# 10-DPLL-1.net
KiCad netlist of a schematic drawn in Altium Designer
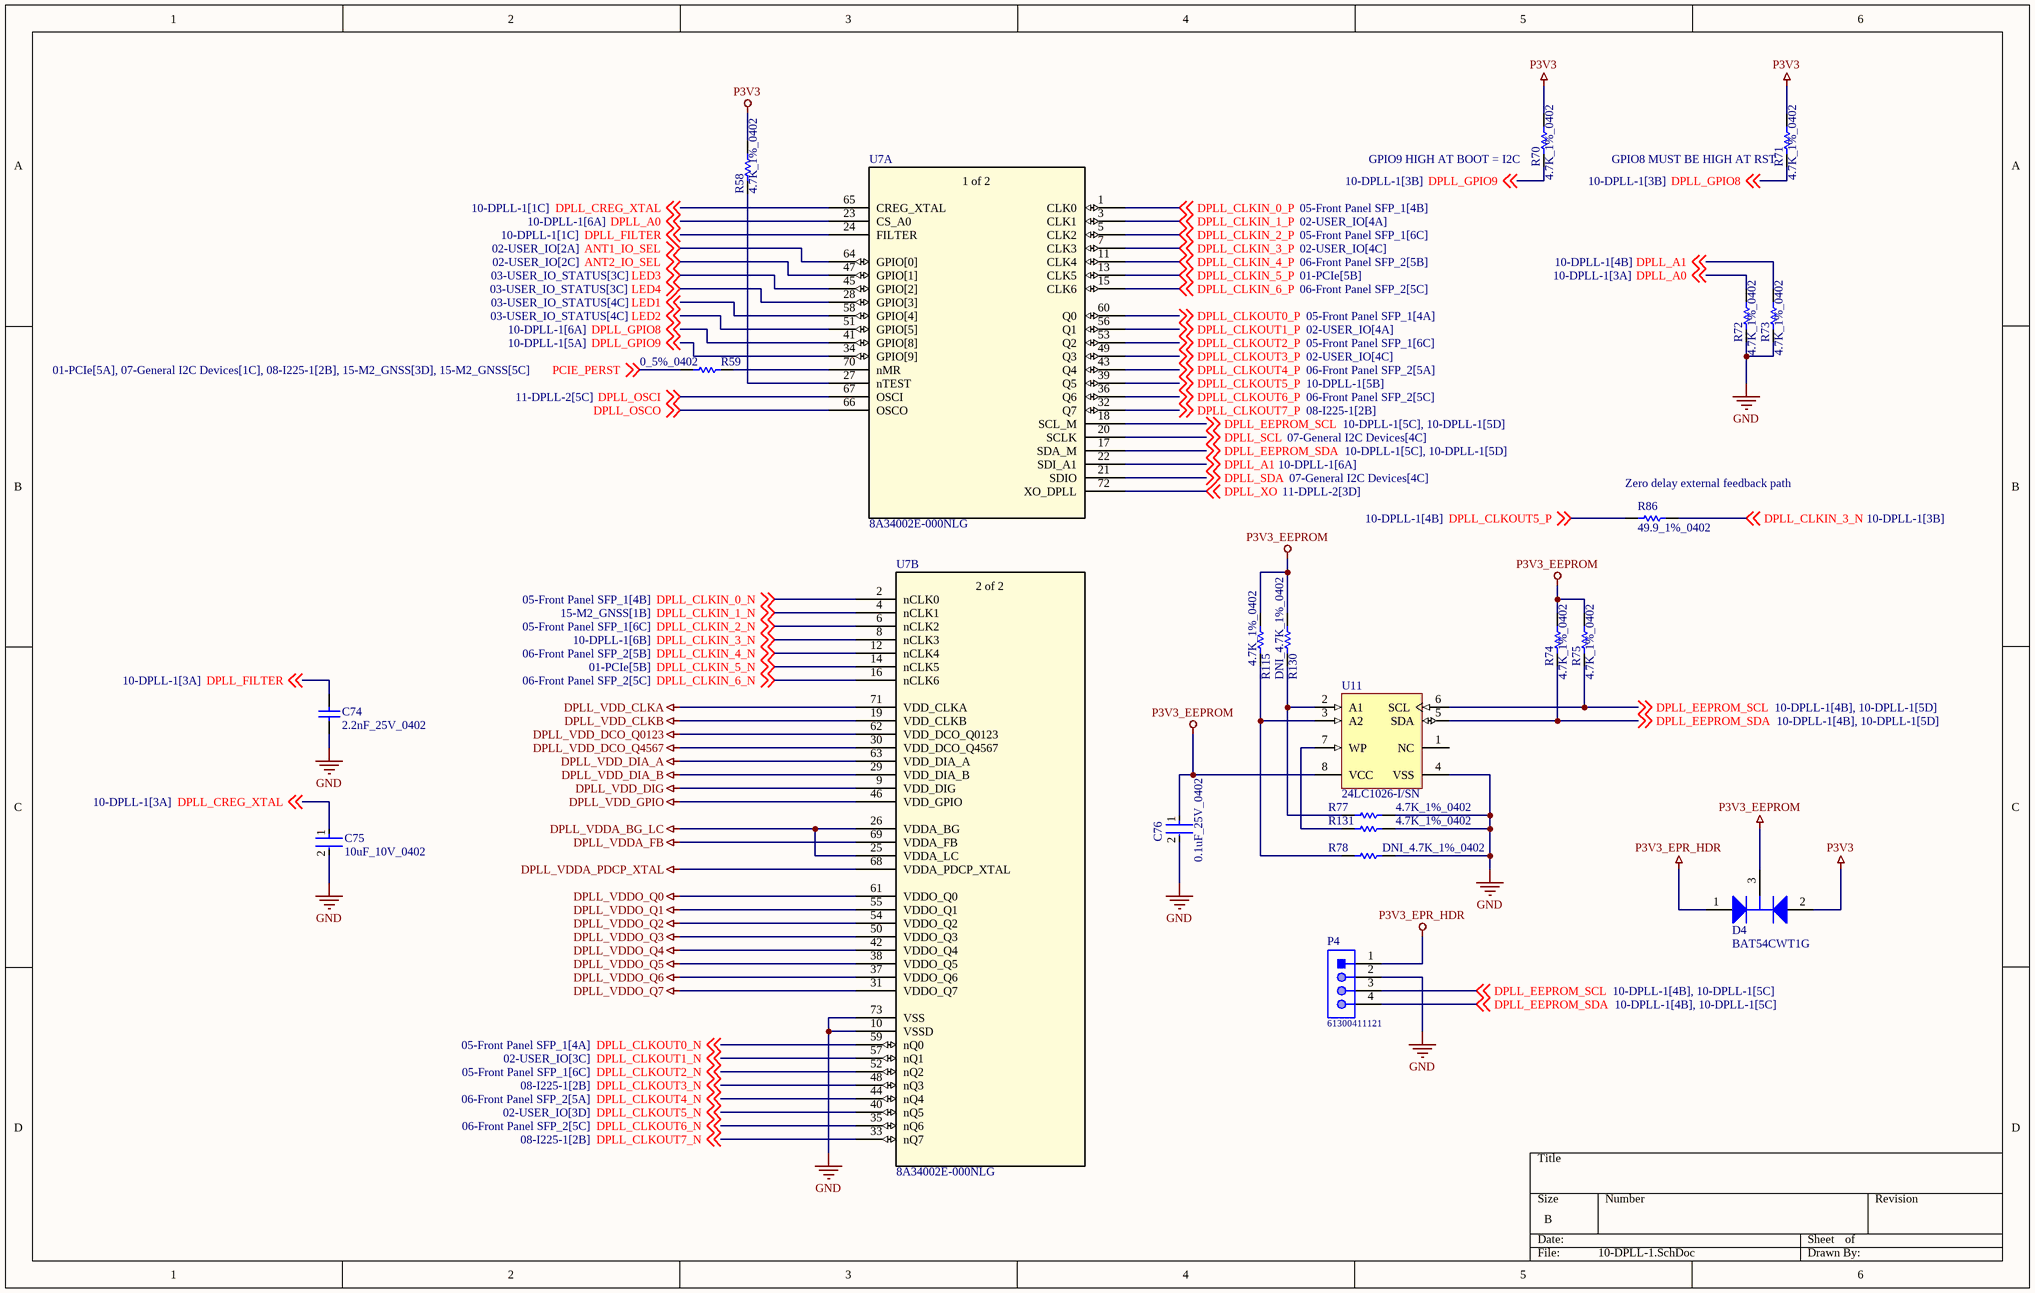
[diagram p0: 10-DPLL-1.SchDoc]

(export (version "E")
  (design (tool "Eeschema 10.0.6"))
  (components
    (comp (ref "C74")
      (value "2.2nF_25V_0402")
      (footprint "CAPC1005X56X25LL10T15")
      (fields
        (field (name "MANUFACTURER") "AVX Interconnect / Elco")
        (field (name "PART NUMBER") "04025C222JAT2A")
      )
      (libsource (lib "Altium Content Vault") (part "CAP"))
    )
    (comp (ref "C75")
      (value "10uF_10V_0402")
      (footprint "FP-CL05A106MP5NUNC-MFG")
      (description "CAP CER 10UF 10V X5R 0402")
      (fields
        (field (name "OCTOPART") "https://octopart.com/cl05a106mp5nunc-samsung-22457395")
        (field (name "TOLERANCE") "20%")
      )
      (libsource (lib "Altium Content Vault") (part "b4654b650e69147ec39a6b967a45e02"))
    )
    (comp (ref "C76")
      (value "0.1uF_25V_0402")
      (footprint "FP-0402-L_1_0_1-W_0_5_0_1-IPC_C")
      (description "General Purpose Ceramic Capacitor, 0402, 100nF, 10%, X7R, 15%, 25V")
      (fields (field (name "VOLTAGE") "25V") (field (name "TOLERANCE") "10%"))
      (libsource (lib "Altium Content Vault") (part "b4654b650e69147ec39a6b967a45e02"))
    )
    (comp (ref "D4")
      (value "BAT54CWT1G")
      (footprint "ONSC-SOT-323-3-419-04_V")
      (description "Dual Series Cathode Schottky Barrier Diodes, 3-Pin SOT-323, Pb-Free, Tape and Reel")
      (fields (field (name "MANUFACTURER") "On Semiconductor"))
      (libsource (lib "Altium Content Vault") (part "ONSC-D-A1A2K3-3"))
    )
    (comp (ref "P4")
      (value "61300411121")
      (footprint "61300411121")
      (description "THT Vertical Pin Header WR-PHD, Pitch 2.54 mm, Single Row, 4 pins")
      (fields (field (name "MANUFACTURER") "Wurth Elektronik") (field (name "PUBLISHER") "WurthElektronik"))
      (libsource (lib "Altium Content Vault") (part "WE-CN-1P-M-R4"))
    )
    (comp (ref "R58")
      (value "4.7K_1%_0402")
      (footprint "RESC1005X40X25NL10T10")
      (fields (field (name "MANUFACTURER") "Bourns") (field (name "PART NUMBER") "CR0402-FX-4701GLF"))
      (libsource (lib "Altium Content Vault") (part "RES"))
    )
    (comp (ref "R59")
      (value "0_5%_0402")
      (footprint "RESC1005X40X25LL10T10")
      (fields (field (name "MANUFACTURER") "KOA Speer") (field (name "PART NUMBER") "RK73Z1ETTP"))
      (libsource (lib "Altium Content Vault") (part "RES"))
    )
    (comp (ref "R70")
      (value "4.7K_1%_0402")
      (footprint "RESC1005X40X25NL10T10")
      (fields (field (name "MANUFACTURER") "Bourns") (field (name "PART NUMBER") "CR0402-FX-4701GLF"))
      (libsource (lib "Altium Content Vault") (part "RES"))
    )
    (comp (ref "R71")
      (value "4.7K_1%_0402")
      (footprint "RESC1005X40X25NL10T10")
      (fields (field (name "MANUFACTURER") "Bourns") (field (name "PART NUMBER") "CR0402-FX-4701GLF"))
      (libsource (lib "Altium Content Vault") (part "RES"))
    )
    (comp (ref "R72")
      (value "4.7K_1%_0402")
      (footprint "RESC1005X40X25NL10T10")
      (fields (field (name "MANUFACTURER") "Bourns") (field (name "PART NUMBER") "CR0402-FX-4701GLF"))
      (libsource (lib "Altium Content Vault") (part "RES"))
    )
    (comp (ref "R73")
      (value "4.7K_1%_0402")
      (footprint "RESC1005X40X25NL10T10")
      (fields (field (name "MANUFACTURER") "Bourns") (field (name "PART NUMBER") "CR0402-FX-4701GLF"))
      (libsource (lib "Altium Content Vault") (part "RES"))
    )
    (comp (ref "R74")
      (value "4.7K_1%_0402")
      (footprint "RESC1005X40X25NL10T10")
      (fields (field (name "MANUFACTURER") "Bourns") (field (name "PART NUMBER") "CR0402-FX-4701GLF"))
      (libsource (lib "Altium Content Vault") (part "RES"))
    )
    (comp (ref "R75")
      (value "4.7K_1%_0402")
      (footprint "RESC1005X40X25NL10T10")
      (fields (field (name "MANUFACTURER") "Bourns") (field (name "PART NUMBER") "CR0402-FX-4701GLF"))
      (libsource (lib "Altium Content Vault") (part "RES"))
    )
    (comp (ref "R77")
      (value "4.7K_1%_0402")
      (footprint "RESC1005X40X25NL10T10")
      (fields (field (name "MANUFACTURER") "Bourns") (field (name "PART NUMBER") "CR0402-FX-4701GLF"))
      (libsource (lib "Altium Content Vault") (part "RES"))
    )
    (comp (ref "R78")
      (value "DNI_4.7K_1%_0402")
      (footprint "RESC1005X40X25NL10T10")
      (fields (field (name "MANUFACTURER") "Bourns") (field (name "PART NUMBER") "CR0402-FX-4701GLF"))
      (libsource (lib "Altium Content Vault") (part "RES"))
    )
    (comp (ref "R86")
      (value "49.9_1%_0402")
      (footprint "RESC1005X40X25NL10T10")
      (fields (field (name "PART NUMBER") "RK73H1ETTP49R9F") (field (name "MANUFACTURER") "KOA Speer"))
      (libsource (lib "Altium Content Vault") (part "RES"))
    )
    (comp (ref "R115")
      (value "4.7K_1%_0402")
      (footprint "RESC1005X40X25NL10T10")
      (fields (field (name "MANUFACTURER") "Bourns") (field (name "PART NUMBER") "CR0402-FX-4701GLF"))
      (libsource (lib "Altium Content Vault") (part "RES"))
    )
    (comp (ref "R130")
      (value "DNI_4.7K_1%_0402")
      (footprint "RESC1005X40X25NL10T10")
      (fields (field (name "MANUFACTURER") "Bourns") (field (name "PART NUMBER") "CR0402-FX-4701GLF"))
      (libsource (lib "Altium Content Vault") (part "RES"))
    )
    (comp (ref "R131")
      (value "4.7K_1%_0402")
      (footprint "RESC1005X40X25NL10T10")
      (fields (field (name "MANUFACTURER") "Bourns") (field (name "PART NUMBER") "CR0402-FX-4701GLF"))
      (libsource (lib "Altium Content Vault") (part "RES"))
    )
    (comp (ref "U7")
      (value "8A34002E-000NLG")
      (footprint "QFN_2E-000NLG_REN")
      (description "No Description Available")
      (libsource (lib "8A34002E-000NLG") (part "8A34002E-000NLG"))
    )
    (comp (ref "U11")
      (value "24LC1026-I/SN")
      (footprint "MCHP-SOIC-SN8_N")
      (description "1024K bits I2C™ Serial EEPROM, 2.5 to 5.5 V, 400 kHz, -40 to 85 degC, 8-pin SOIC (SN8), Tube")
      (fields (field (name "MANUFACTURER") "Microchip"))
      (libsource (lib "Altium Content Vault") (part "MCHP-24LC1026-SOIC-8"))
    )
  )
  (nets
    (net (code "1") (name "ANT1_IO_SEL") (class "Default")
      (node (ref "U7") (pin "64") (pinfunction "GPIO[0]_64") (pintype "bidirectional"))
    )
    (net (code "2") (name "ANT2_IO_SEL") (class "Default")
      (node (ref "U7") (pin "47") (pinfunction "GPIO[1]_47") (pintype "bidirectional"))
    )
    (net (code "3") (name "DPLL_A0") (class "Default")
      (node (ref "R72") (pin "1") (pinfunction "1_1") (pintype "passive"))
      (node (ref "U7") (pin "23") (pinfunction "CS_A0_23") (pintype "passive"))
    )
    (net (code "4") (name "DPLL_A1") (class "Default")
      (node (ref "R73") (pin "1") (pinfunction "1_1") (pintype "passive"))
      (node (ref "U7") (pin "22") (pinfunction "SDI_A1_22") (pintype "passive"))
    )
    (net (code "5") (name "DPLL_CLKIN_0_N") (class "Default")
      (node (ref "U7") (pin "2") (pinfunction "nCLK0_2") (pintype "passive"))
    )
    (net (code "6") (name "DPLL_CLKIN_0_P") (class "Default")
      (node (ref "U7") (pin "1") (pinfunction "CLK0_1") (pintype "bidirectional"))
    )
    (net (code "7") (name "DPLL_CLKIN_1_N") (class "Default")
      (node (ref "U7") (pin "4") (pinfunction "nCLK1_4") (pintype "passive"))
    )
    (net (code "8") (name "DPLL_CLKIN_1_P") (class "Default")
      (node (ref "U7") (pin "3") (pinfunction "CLK1_3") (pintype "bidirectional"))
    )
    (net (code "9") (name "DPLL_CLKIN_2_N") (class "Default")
      (node (ref "U7") (pin "6") (pinfunction "nCLK2_6") (pintype "passive"))
    )
    (net (code "10") (name "DPLL_CLKIN_2_P") (class "Default")
      (node (ref "U7") (pin "5") (pinfunction "CLK2_5") (pintype "bidirectional"))
    )
    (net (code "11") (name "DPLL_CLKIN_3_N") (class "Default")
      (node (ref "R86") (pin "2") (pinfunction "2_2") (pintype "passive"))
      (node (ref "U7") (pin "8") (pinfunction "nCLK3_8") (pintype "passive"))
    )
    (net (code "12") (name "DPLL_CLKIN_3_P") (class "Default")
      (node (ref "U7") (pin "7") (pinfunction "CLK3_7") (pintype "bidirectional"))
    )
    (net (code "13") (name "DPLL_CLKIN_4_N") (class "Default")
      (node (ref "U7") (pin "12") (pinfunction "nCLK4_12") (pintype "passive"))
    )
    (net (code "14") (name "DPLL_CLKIN_4_P") (class "Default")
      (node (ref "U7") (pin "11") (pinfunction "CLK4_11") (pintype "bidirectional"))
    )
    (net (code "15") (name "DPLL_CLKIN_5_N") (class "Default")
      (node (ref "U7") (pin "14") (pinfunction "nCLK5_14") (pintype "passive"))
    )
    (net (code "16") (name "DPLL_CLKIN_5_P") (class "Default")
      (node (ref "U7") (pin "13") (pinfunction "CLK5_13") (pintype "bidirectional"))
    )
    (net (code "17") (name "DPLL_CLKIN_6_N") (class "Default")
      (node (ref "U7") (pin "16") (pinfunction "nCLK6_16") (pintype "passive"))
    )
    (net (code "18") (name "DPLL_CLKIN_6_P") (class "Default")
      (node (ref "U7") (pin "15") (pinfunction "CLK6_15") (pintype "bidirectional"))
    )
    (net (code "19") (name "DPLL_CLKOUT0_N") (class "Default")
      (node (ref "U7") (pin "59") (pinfunction "nQ0_59") (pintype "bidirectional"))
    )
    (net (code "20") (name "DPLL_CLKOUT0_P") (class "Default")
      (node (ref "U7") (pin "60") (pinfunction "Q0_60") (pintype "bidirectional"))
    )
    (net (code "21") (name "DPLL_CLKOUT1_N") (class "Default")
      (node (ref "U7") (pin "57") (pinfunction "nQ1_57") (pintype "bidirectional"))
    )
    (net (code "22") (name "DPLL_CLKOUT1_P") (class "Default")
      (node (ref "U7") (pin "56") (pinfunction "Q1_56") (pintype "bidirectional"))
    )
    (net (code "23") (name "DPLL_CLKOUT2_N") (class "Default")
      (node (ref "U7") (pin "52") (pinfunction "nQ2_52") (pintype "bidirectional"))
    )
    (net (code "24") (name "DPLL_CLKOUT2_P") (class "Default")
      (node (ref "U7") (pin "53") (pinfunction "Q2_53") (pintype "bidirectional"))
    )
    (net (code "25") (name "DPLL_CLKOUT3_N") (class "Default")
      (node (ref "U7") (pin "48") (pinfunction "nQ3_48") (pintype "bidirectional"))
    )
    (net (code "26") (name "DPLL_CLKOUT3_P") (class "Default")
      (node (ref "U7") (pin "49") (pinfunction "Q3_49") (pintype "bidirectional"))
    )
    (net (code "27") (name "DPLL_CLKOUT4_N") (class "Default")
      (node (ref "U7") (pin "44") (pinfunction "nQ4_44") (pintype "bidirectional"))
    )
    (net (code "28") (name "DPLL_CLKOUT4_P") (class "Default")
      (node (ref "U7") (pin "43") (pinfunction "Q4_43") (pintype "bidirectional"))
    )
    (net (code "29") (name "DPLL_CLKOUT5_N") (class "Default")
      (node (ref "U7") (pin "40") (pinfunction "nQ5_40") (pintype "bidirectional"))
    )
    (net (code "30") (name "DPLL_CLKOUT5_P") (class "Default")
      (node (ref "R86") (pin "1") (pinfunction "1_1") (pintype "passive"))
      (node (ref "U7") (pin "39") (pinfunction "Q5_39") (pintype "bidirectional"))
    )
    (net (code "31") (name "DPLL_CLKOUT6_N") (class "Default")
      (node (ref "U7") (pin "35") (pinfunction "nQ6_35") (pintype "bidirectional"))
    )
    (net (code "32") (name "DPLL_CLKOUT6_P") (class "Default")
      (node (ref "U7") (pin "36") (pinfunction "Q6_36") (pintype "bidirectional"))
    )
    (net (code "33") (name "DPLL_CLKOUT7_N") (class "Default")
      (node (ref "U7") (pin "33") (pinfunction "nQ7_33") (pintype "bidirectional"))
    )
    (net (code "34") (name "DPLL_CLKOUT7_P") (class "Default")
      (node (ref "U7") (pin "32") (pinfunction "Q7_32") (pintype "bidirectional"))
    )
    (net (code "35") (name "DPLL_CREG_XTAL") (class "Default")
      (node (ref "C75") (pin "1") (pinfunction "1_1") (pintype "passive"))
      (node (ref "U7") (pin "65") (pinfunction "CREG_XTAL_65") (pintype "passive"))
    )
    (net (code "36") (name "DPLL_EEPROM_SCL") (class "Default")
      (node (ref "P4") (pin "3") (pinfunction "3_3") (pintype "passive"))
      (node (ref "R75") (pin "2") (pinfunction "2_2") (pintype "passive"))
      (node (ref "U11") (pin "6") (pinfunction "SCL_6") (pintype "input"))
      (node (ref "U7") (pin "18") (pinfunction "SCL_M_18") (pintype "passive"))
    )
    (net (code "37") (name "DPLL_EEPROM_SDA") (class "Default")
      (node (ref "P4") (pin "4") (pinfunction "4_4") (pintype "passive"))
      (node (ref "R74") (pin "2") (pinfunction "2_2") (pintype "passive"))
      (node (ref "U11") (pin "5") (pinfunction "SDA_5") (pintype "bidirectional"))
      (node (ref "U7") (pin "17") (pinfunction "SDA_M_17") (pintype "passive"))
    )
    (net (code "38") (name "DPLL_FILTER") (class "Default")
      (node (ref "C74") (pin "2") (pinfunction "2_2") (pintype "passive"))
      (node (ref "U7") (pin "24") (pinfunction "FILTER_24") (pintype "passive"))
    )
    (net (code "39") (name "DPLL_GPIO8") (class "Default")
      (node (ref "R71") (pin "2") (pinfunction "2_2") (pintype "passive"))
      (node (ref "U7") (pin "41") (pinfunction "GPIO[8]_41") (pintype "bidirectional"))
    )
    (net (code "40") (name "DPLL_GPIO9") (class "Default")
      (node (ref "R70") (pin "2") (pinfunction "2_2") (pintype "passive"))
      (node (ref "U7") (pin "34") (pinfunction "GPIO[9]_34") (pintype "bidirectional"))
    )
    (net (code "41") (name "DPLL_OSCI") (class "Default")
      (node (ref "U7") (pin "67") (pinfunction "OSCI_67") (pintype "passive"))
    )
    (net (code "42") (name "DPLL_OSCO") (class "Default")
      (node (ref "U7") (pin "66") (pinfunction "OSCO_66") (pintype "passive"))
    )
    (net (code "43") (name "DPLL_SCL") (class "Default")
      (node (ref "U7") (pin "20") (pinfunction "SCLK_20") (pintype "passive"))
    )
    (net (code "44") (name "DPLL_SDA") (class "Default")
      (node (ref "U7") (pin "21") (pinfunction "SDIO_21") (pintype "passive"))
    )
    (net (code "45") (name "DPLL_VDDA_BG_LC") (class "Default")
      (node (ref "U7") (pin "25") (pinfunction "VDDA_LC_25") (pintype "power_in"))
      (node (ref "U7") (pin "26") (pinfunction "VDDA_BG_26") (pintype "power_in"))
    )
    (net (code "46") (name "DPLL_VDDA_FB") (class "Default")
      (node (ref "U7") (pin "69") (pinfunction "VDDA_FB_69") (pintype "power_in"))
    )
    (net (code "47") (name "DPLL_VDDA_PDCP_XTAL") (class "Default")
      (node (ref "U7") (pin "68") (pinfunction "VDDA_PDCP_XTAL_68") (pintype "power_in"))
    )
    (net (code "48") (name "DPLL_VDDO_Q0") (class "Default")
      (node (ref "U7") (pin "61") (pinfunction "VDDO_Q0_61") (pintype "power_in"))
    )
    (net (code "49") (name "DPLL_VDDO_Q1") (class "Default")
      (node (ref "U7") (pin "55") (pinfunction "VDDO_Q1_55") (pintype "power_in"))
    )
    (net (code "50") (name "DPLL_VDDO_Q2") (class "Default")
      (node (ref "U7") (pin "54") (pinfunction "VDDO_Q2_54") (pintype "power_in"))
    )
    (net (code "51") (name "DPLL_VDDO_Q3") (class "Default")
      (node (ref "U7") (pin "50") (pinfunction "VDDO_Q3_50") (pintype "power_in"))
    )
    (net (code "52") (name "DPLL_VDDO_Q4") (class "Default")
      (node (ref "U7") (pin "42") (pinfunction "VDDO_Q4_42") (pintype "power_in"))
    )
    (net (code "53") (name "DPLL_VDDO_Q5") (class "Default")
      (node (ref "U7") (pin "38") (pinfunction "VDDO_Q5_38") (pintype "power_in"))
    )
    (net (code "54") (name "DPLL_VDDO_Q6") (class "Default")
      (node (ref "U7") (pin "37") (pinfunction "VDDO_Q6_37") (pintype "power_in"))
    )
    (net (code "55") (name "DPLL_VDDO_Q7") (class "Default")
      (node (ref "U7") (pin "31") (pinfunction "VDDO_Q7_31") (pintype "power_in"))
    )
    (net (code "56") (name "DPLL_VDD_CLKA") (class "Default")
      (node (ref "U7") (pin "71") (pinfunction "VDD_CLKA_71") (pintype "power_in"))
    )
    (net (code "57") (name "DPLL_VDD_CLKB") (class "Default")
      (node (ref "U7") (pin "19") (pinfunction "VDD_CLKB_19") (pintype "power_in"))
    )
    (net (code "58") (name "DPLL_VDD_DCO_Q0123") (class "Default")
      (node (ref "U7") (pin "62") (pinfunction "VDD_DCO_Q0123_62") (pintype "power_in"))
    )
    (net (code "59") (name "DPLL_VDD_DCO_Q4567") (class "Default")
      (node (ref "U7") (pin "30") (pinfunction "VDD_DCO_Q4567_30") (pintype "power_in"))
    )
    (net (code "60") (name "DPLL_VDD_DIA_A") (class "Default")
      (node (ref "U7") (pin "63") (pinfunction "VDD_DIA_A_63") (pintype "power_in"))
    )
    (net (code "61") (name "DPLL_VDD_DIA_B") (class "Default")
      (node (ref "U7") (pin "29") (pinfunction "VDD_DIA_B_29") (pintype "power_in"))
    )
    (net (code "62") (name "DPLL_VDD_DIG") (class "Default")
      (node (ref "U7") (pin "9") (pinfunction "VDD_DIG_9") (pintype "power_in"))
    )
    (net (code "63") (name "DPLL_VDD_GPIO") (class "Default")
      (node (ref "U7") (pin "46") (pinfunction "VDD_GPIO_46") (pintype "power_in"))
    )
    (net (code "64") (name "DPLL_XO") (class "Default")
      (node (ref "U7") (pin "72") (pinfunction "XO_DPLL_72") (pintype "passive"))
    )
    (net (code "65") (name "GND") (class "Default")
      (node (ref "C74") (pin "1") (pinfunction "1_1") (pintype "passive"))
      (node (ref "C75") (pin "2") (pinfunction "2_2") (pintype "passive"))
      (node (ref "C76") (pin "2") (pinfunction "2_2") (pintype "passive"))
      (node (ref "P4") (pin "2") (pinfunction "2_2") (pintype "passive"))
      (node (ref "R131") (pin "1") (pinfunction "1_1") (pintype "passive"))
      (node (ref "R72") (pin "2") (pinfunction "2_2") (pintype "passive"))
      (node (ref "R73") (pin "2") (pinfunction "2_2") (pintype "passive"))
      (node (ref "R77") (pin "1") (pinfunction "1_1") (pintype "passive"))
      (node (ref "R78") (pin "2") (pinfunction "2_2") (pintype "passive"))
      (node (ref "U11") (pin "4") (pinfunction "VSS_4") (pintype "power_in"))
      (node (ref "U7") (pin "10") (pinfunction "VSSD_10") (pintype "power_in"))
      (node (ref "U7") (pin "73") (pinfunction "VSS_73") (pintype "power_in"))
    )
    (net (code "66") (name "LED1") (class "Default")
      (node (ref "U7") (pin "58") (pinfunction "GPIO[4]_58") (pintype "bidirectional"))
    )
    (net (code "67") (name "LED2") (class "Default")
      (node (ref "U7") (pin "51") (pinfunction "GPIO[5]_51") (pintype "bidirectional"))
    )
    (net (code "68") (name "LED3") (class "Default")
      (node (ref "U7") (pin "45") (pinfunction "GPIO[2]_45") (pintype "bidirectional"))
    )
    (net (code "69") (name "LED4") (class "Default")
      (node (ref "U7") (pin "28") (pinfunction "GPIO[3]_28") (pintype "bidirectional"))
    )
    (net (code "70") (name "Net-(U7A-nMR)") (class "Default")
      (node (ref "R59") (pin "2") (pinfunction "2_2") (pintype "passive"))
      (node (ref "U7") (pin "70") (pinfunction "nMR_70") (pintype "passive"))
    )
    (net (code "71") (name "Net-(U7A-nTEST)") (class "Default")
      (node (ref "R58") (pin "1") (pinfunction "1_1") (pintype "passive"))
      (node (ref "U7") (pin "27") (pinfunction "nTEST_27") (pintype "passive"))
    )
    (net (code "72") (name "Net-(U11-A1)") (class "Default")
      (node (ref "R130") (pin "1") (pinfunction "1_1") (pintype "passive"))
      (node (ref "R77") (pin "2") (pinfunction "2_2") (pintype "passive"))
      (node (ref "U11") (pin "2") (pinfunction "A1_2") (pintype "input"))
    )
    (net (code "73") (name "Net-(U11-A2)") (class "Default")
      (node (ref "R115") (pin "1") (pinfunction "1_1") (pintype "passive"))
      (node (ref "R78") (pin "1") (pinfunction "1_1") (pintype "passive"))
      (node (ref "U11") (pin "3") (pinfunction "A2_3") (pintype "input"))
    )
    (net (code "74") (name "Net-(U11-WP)") (class "Default")
      (node (ref "R131") (pin "2") (pinfunction "2_2") (pintype "passive"))
      (node (ref "U11") (pin "7") (pinfunction "WP_7") (pintype "input"))
    )
    (net (code "75") (name "P3V3") (class "Default")
      (node (ref "D4") (pin "2") (pinfunction "A2_2") (pintype "passive"))
      (node (ref "R58") (pin "2") (pinfunction "2_2") (pintype "passive"))
      (node (ref "R70") (pin "1") (pinfunction "1_1") (pintype "passive"))
      (node (ref "R71") (pin "1") (pinfunction "1_1") (pintype "passive"))
    )
    (net (code "76") (name "P3V3_EEPROM") (class "Default")
      (node (ref "C76") (pin "1") (pinfunction "1_1") (pintype "passive"))
      (node (ref "D4") (pin "3") (pinfunction "K_3") (pintype "passive"))
      (node (ref "R115") (pin "2") (pinfunction "2_2") (pintype "passive"))
      (node (ref "R130") (pin "2") (pinfunction "2_2") (pintype "passive"))
      (node (ref "R74") (pin "1") (pinfunction "1_1") (pintype "passive"))
      (node (ref "R75") (pin "1") (pinfunction "1_1") (pintype "passive"))
      (node (ref "U11") (pin "8") (pinfunction "VCC_8") (pintype "power_in"))
    )
    (net (code "77") (name "P3V3_EPR_HDR") (class "Default")
      (node (ref "D4") (pin "1") (pinfunction "A1_1") (pintype "passive"))
      (node (ref "P4") (pin "1") (pinfunction "1_1") (pintype "passive"))
    )
    (net (code "78") (name "PCIE_PERST") (class "Default")
      (node (ref "R59") (pin "1") (pinfunction "1_1") (pintype "passive"))
    )
    (net (code "79") (name "unconnected-(U11-NC-Pad1)") (class "Default")
      (node (ref "U11") (pin "1") (pinfunction "NC_1") (pintype "passive"))
    )
  )
)
